# lcd_et_rotary.net
KiCad netlist of a schematic drawn in EAGLE
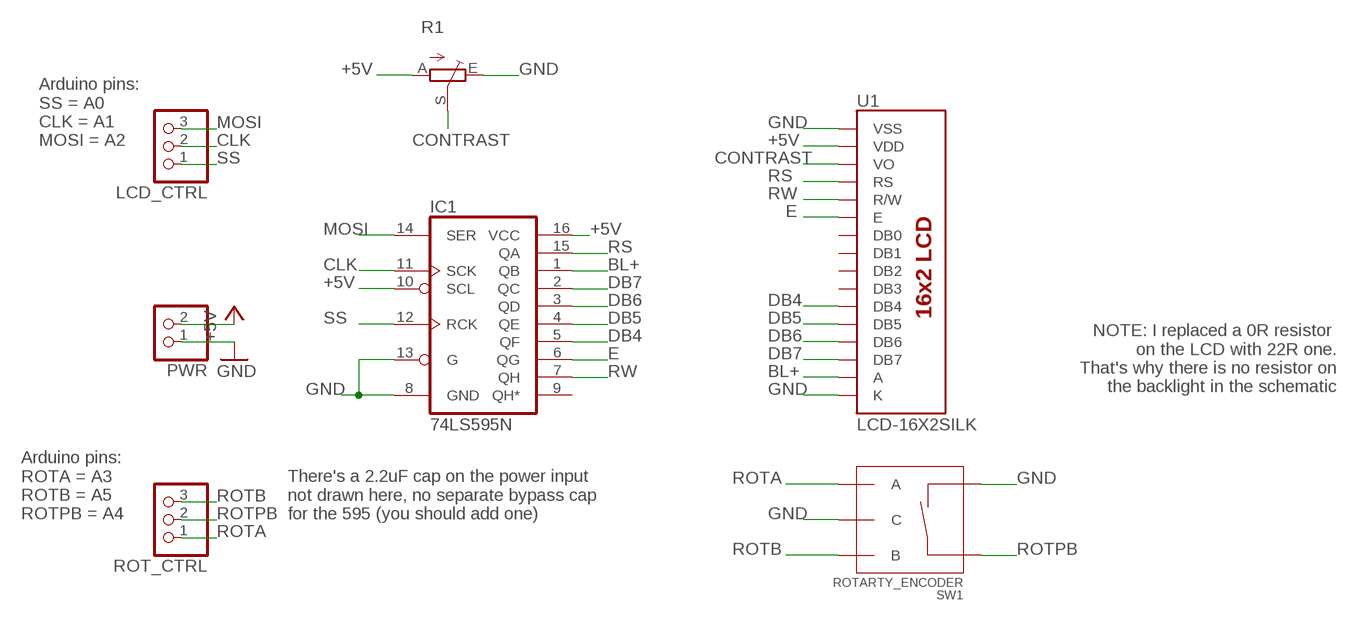
[diagram p0: schematic, sheet 1]

(export (version "E")
  (design (tool "Eeschema 10.0.6"))
  (components
    (comp (ref "IC1")
      (value "74LS595N")
      (footprint "eagle-import:DIL16")
      (libsource (lib "eagle-import") (part "74595NLS"))
    )
    (comp (ref "LCD_CTRL")
      (value "PINHD-1X3")
      (footprint "eagle-import:1X03")
      (libsource (lib "eagle-import") (part "PINHD-1X3"))
    )
    (comp (ref "PWR")
      (value "PINHD-1X2")
      (footprint "eagle-import:1X02")
      (libsource (lib "eagle-import") (part "PINHD-1X2"))
    )
    (comp (ref "R1")
      (value "TRIM_EU-S64W")
      (footprint "eagle-import:S64W")
      (libsource (lib "eagle-import") (part "TRIM_EU-S64W"))
    )
    (comp (ref "ROT_CTRL")
      (value "PINHD-1X3")
      (footprint "eagle-import:1X03")
      (libsource (lib "eagle-import") (part "PINHD-1X3"))
    )
    (comp (ref "SW1")
      (value "ROTARTY_ENCODER")
      (footprint "eagle-import:ROTARY_ENC_PLAIN")
      (libsource (lib "eagle-import") (part "ROTARTY_ENCODER"))
    )
    (comp (ref "U1")
      (value "LCD-16X2SILK")
      (footprint "eagle-import:LCD-16X2")
      (libsource (lib "eagle-import") (part "LCD-16X2SILK"))
    )
  )
  (nets
    (net (code "1") (name "+5V") (class "Default")
      (node (ref "IC1") (pin "10") (pinfunction "SCL_10") (pintype "input"))
      (node (ref "IC1") (pin "16") (pinfunction "VCC_16") (pintype "power_in"))
      (node (ref "PWR") (pin "2") (pinfunction "2_2") (pintype "passive"))
      (node (ref "R1") (pin "A") (pinfunction "A_A") (pintype "passive"))
      (node (ref "U1") (pin "2") (pinfunction "VDD_2") (pintype "power_in"))
    )
    (net (code "2") (name "/BL+") (class "Default")
      (node (ref "IC1") (pin "1") (pinfunction "QB_1") (pintype "tri_state"))
      (node (ref "U1") (pin "15") (pinfunction "A_15") (pintype "power_in"))
    )
    (net (code "3") (name "/CLK") (class "Default")
      (node (ref "IC1") (pin "11") (pinfunction "SCK_11") (pintype "input"))
      (node (ref "LCD_CTRL") (pin "2") (pinfunction "2_2") (pintype "passive"))
    )
    (net (code "4") (name "/CONTRAST") (class "Default")
      (node (ref "R1") (pin "S") (pinfunction "S_S") (pintype "passive"))
      (node (ref "U1") (pin "3") (pinfunction "VO_3") (pintype "bidirectional"))
    )
    (net (code "5") (name "/DB4") (class "Default")
      (node (ref "IC1") (pin "5") (pinfunction "QF_5") (pintype "tri_state"))
      (node (ref "U1") (pin "11") (pinfunction "DB4_11") (pintype "bidirectional"))
    )
    (net (code "6") (name "/DB5") (class "Default")
      (node (ref "IC1") (pin "4") (pinfunction "QE_4") (pintype "tri_state"))
      (node (ref "U1") (pin "12") (pinfunction "DB5_12") (pintype "bidirectional"))
    )
    (net (code "7") (name "/DB6") (class "Default")
      (node (ref "IC1") (pin "3") (pinfunction "QD_3") (pintype "tri_state"))
      (node (ref "U1") (pin "13") (pinfunction "DB6_13") (pintype "bidirectional"))
    )
    (net (code "8") (name "/DB7") (class "Default")
      (node (ref "IC1") (pin "2") (pinfunction "QC_2") (pintype "tri_state"))
      (node (ref "U1") (pin "14") (pinfunction "DB7_14") (pintype "bidirectional"))
    )
    (net (code "9") (name "/E") (class "Default")
      (node (ref "IC1") (pin "6") (pinfunction "QG_6") (pintype "tri_state"))
      (node (ref "U1") (pin "6") (pinfunction "E_6") (pintype "input"))
    )
    (net (code "10") (name "/MOSI") (class "Default")
      (node (ref "IC1") (pin "14") (pinfunction "SER_14") (pintype "input"))
      (node (ref "LCD_CTRL") (pin "3") (pinfunction "3_3") (pintype "passive"))
    )
    (net (code "11") (name "/ROTA") (class "Default")
      (node (ref "ROT_CTRL") (pin "1") (pinfunction "1_1") (pintype "passive"))
      (node (ref "SW1") (pin "A") (pinfunction "A_A") (pintype "bidirectional"))
    )
    (net (code "12") (name "/ROTB") (class "Default")
      (node (ref "ROT_CTRL") (pin "3") (pinfunction "3_3") (pintype "passive"))
      (node (ref "SW1") (pin "B") (pinfunction "B_B") (pintype "bidirectional"))
    )
    (net (code "13") (name "/ROTPB") (class "Default")
      (node (ref "ROT_CTRL") (pin "2") (pinfunction "2_2") (pintype "passive"))
      (node (ref "SW1") (pin "SW+") (pinfunction "SW+_SW+") (pintype "bidirectional"))
    )
    (net (code "14") (name "/RS") (class "Default")
      (node (ref "IC1") (pin "15") (pinfunction "QA_15") (pintype "tri_state"))
      (node (ref "U1") (pin "4") (pinfunction "RS_4") (pintype "input"))
    )
    (net (code "15") (name "/RW") (class "Default")
      (node (ref "IC1") (pin "7") (pinfunction "QH_7") (pintype "tri_state"))
      (node (ref "U1") (pin "5") (pinfunction "R/W_5") (pintype "input"))
    )
    (net (code "16") (name "/SS") (class "Default")
      (node (ref "IC1") (pin "12") (pinfunction "RCK_12") (pintype "input"))
      (node (ref "LCD_CTRL") (pin "1") (pinfunction "1_1") (pintype "passive"))
    )
    (net (code "17") (name "GND") (class "Default")
      (node (ref "IC1") (pin "13") (pinfunction "G_13") (pintype "input"))
      (node (ref "IC1") (pin "8") (pinfunction "GND_8") (pintype "power_in"))
      (node (ref "PWR") (pin "1") (pinfunction "1_1") (pintype "passive"))
      (node (ref "R1") (pin "E") (pinfunction "E_E") (pintype "passive"))
      (node (ref "SW1") (pin "C") (pinfunction "C_C") (pintype "bidirectional"))
      (node (ref "SW1") (pin "SW-") (pinfunction "SW-_SW-") (pintype "bidirectional"))
      (node (ref "U1") (pin "1") (pinfunction "VSS_1") (pintype "power_in"))
      (node (ref "U1") (pin "16") (pinfunction "K_16") (pintype "power_in"))
    )
    (net (code "18") (name "unconnected-(IC1-QH*-Pad9)") (class "Default")
      (node (ref "IC1") (pin "9") (pinfunction "QH*_9") (pintype "tri_state"))
    )
    (net (code "19") (name "unconnected-(U1-DB0-Pad7)") (class "Default")
      (node (ref "U1") (pin "7") (pinfunction "DB0_7") (pintype "bidirectional"))
    )
    (net (code "20") (name "unconnected-(U1-DB1-Pad8)") (class "Default")
      (node (ref "U1") (pin "8") (pinfunction "DB1_8") (pintype "bidirectional"))
    )
    (net (code "21") (name "unconnected-(U1-DB2-Pad9)") (class "Default")
      (node (ref "U1") (pin "9") (pinfunction "DB2_9") (pintype "bidirectional"))
    )
    (net (code "22") (name "unconnected-(U1-DB3-Pad10)") (class "Default")
      (node (ref "U1") (pin "10") (pinfunction "DB3_10") (pintype "bidirectional"))
    )
  )
)
